# SCH_SCore-SR1_2024-12-18.net
KiCad netlist of a schematic drawn in EasyEDA
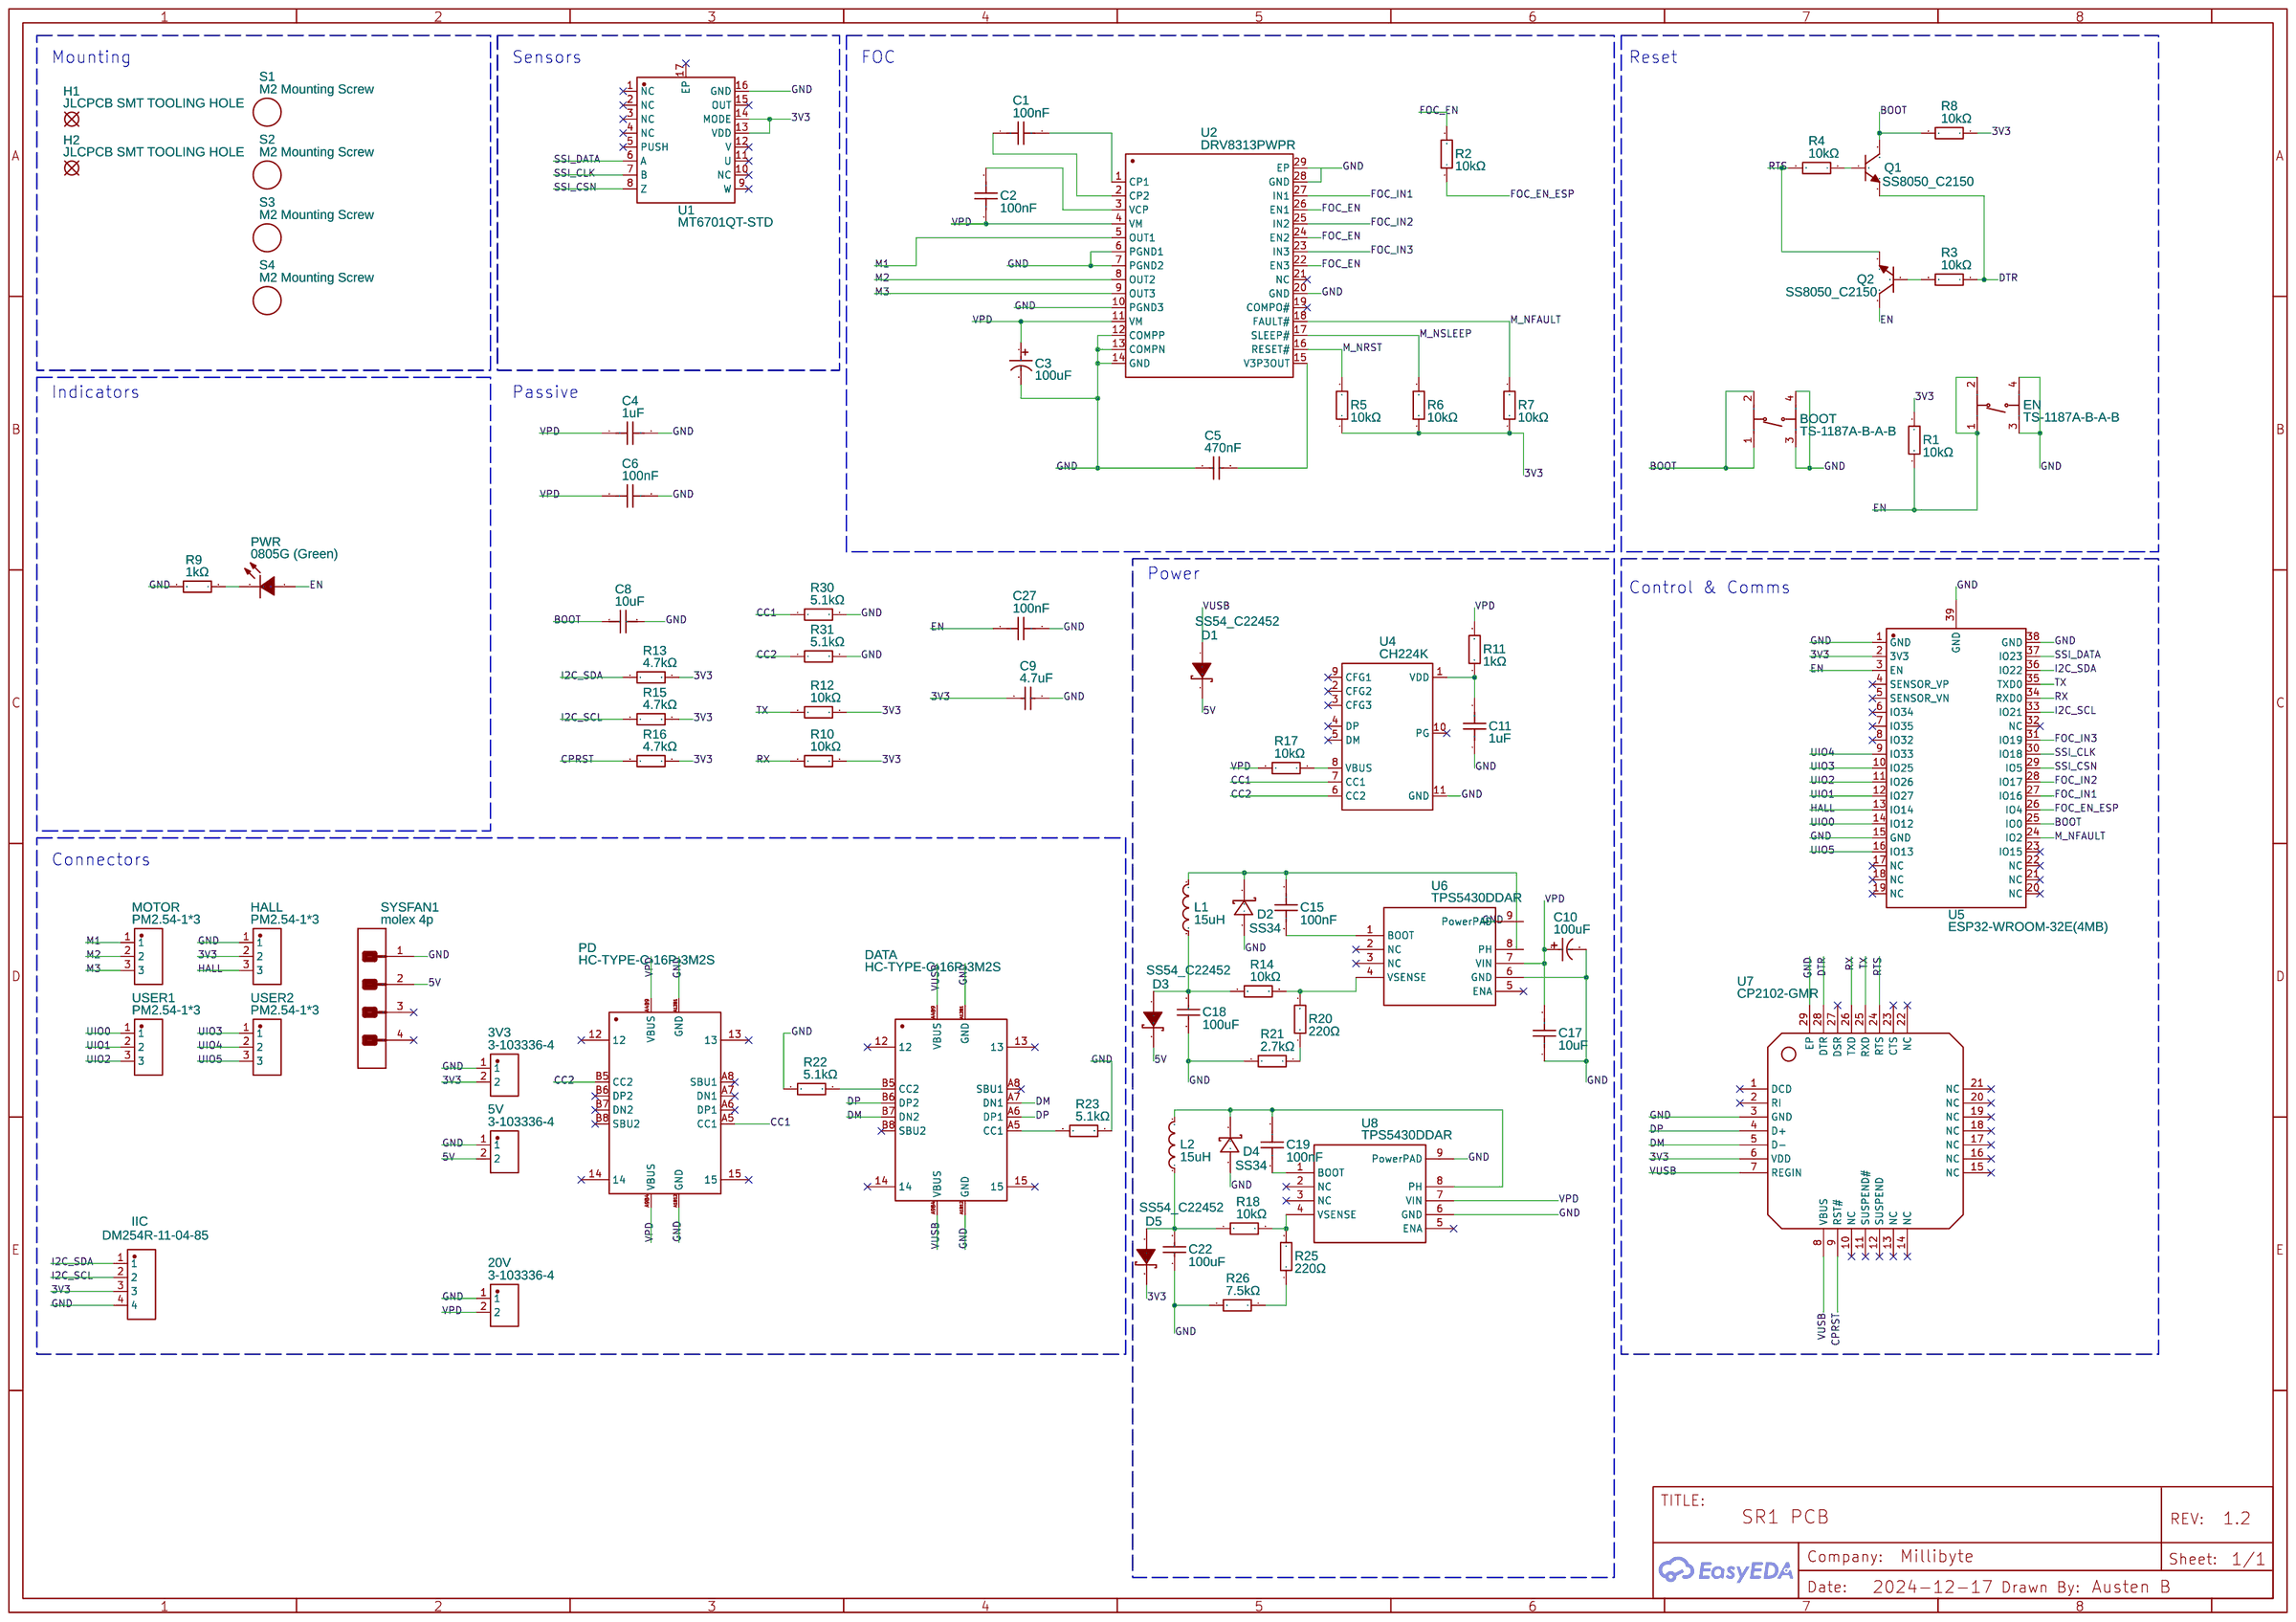
[diagram p0: schematic sheet]

(export (version "E")
  (design (tool "Eeschema 10.0.6"))
  (components
    (comp (ref "3V3")
      (value "3-103336-4")
      (fields (field (name "Manufacturer") "TE Connectivity(泰科电子)"))
      (libsource (lib "") (part "3-103336-4"))
    )
    (comp (ref "5V")
      (value "3-103336-4")
      (fields (field (name "Manufacturer") "TE Connectivity(泰科电子)"))
      (libsource (lib "") (part "3-103336-4_2"))
    )
    (comp (ref "20V")
      (value "3-103336-4")
      (fields (field (name "Manufacturer") "TE Connectivity(泰科电子)"))
      (libsource (lib "") (part "3-103336-4_1"))
    )
    (comp (ref "BOOT")
      (value "TS-1187A-B-A-B")
      (fields (field (name "Manufacturer") "XKB Connectivity(中国星坤)"))
      (libsource (lib "") (part "TS-1187A-B-A-B_1"))
    )
    (comp (ref "C1")
      (value "100nF")
      (fields
        (field (name "Manufacturer Part") "CC0603KRX7R9BB104")
        (field (name "Manufacturer") "YAGEO(国巨)")
      )
      (libsource (lib "") (part "CC0603KRX7R9BB104"))
    )
    (comp (ref "C2")
      (value "100nF")
      (fields
        (field (name "Manufacturer Part") "CC0603KRX7R9BB104")
        (field (name "Manufacturer") "YAGEO(国巨)")
      )
      (libsource (lib "") (part "CC0603KRX7R9BB104_2"))
    )
    (comp (ref "C3")
      (value "100uF")
      (fields (field (name "Manufacturer Part") "RT1V101M0607") (field (name "Manufacturer") "ROQANG(容强)"))
      (libsource (lib "") (part "RT1V101M0607"))
    )
    (comp (ref "C4")
      (value "1uF")
      (fields
        (field (name "Manufacturer Part") "CL10A105KB8NNNC")
        (field (name "Manufacturer") "SAMSUNG(三星)")
      )
      (libsource (lib "") (part "CL10A105KB8NNNC"))
    )
    (comp (ref "C5")
      (value "470nF")
      (fields
        (field (name "Manufacturer Part") "CL21B474KBFNNNE")
        (field (name "Manufacturer") "SAMSUNG(三星)")
      )
      (libsource (lib "") (part "CL21B474KBFNNNE"))
    )
    (comp (ref "C6")
      (value "100nF")
      (fields
        (field (name "Manufacturer Part") "CC0603KRX7R9BB104")
        (field (name "Manufacturer") "YAGEO(国巨)")
      )
      (libsource (lib "") (part "CC0603KRX7R9BB104"))
    )
    (comp (ref "C8")
      (value "10uF")
      (fields
        (field (name "Manufacturer Part") "CL10A106KP8NNNC")
        (field (name "Manufacturer") "SAMSUNG(三星)")
      )
      (libsource (lib "") (part "CL10A106KP8NNNC"))
    )
    (comp (ref "C9")
      (value "4.7uF")
      (fields
        (field (name "Manufacturer Part") "CL05A475MP5NRNC")
        (field (name "Manufacturer") "SAMSUNG(三星)")
      )
      (libsource (lib "") (part "CL05A475MP5NRNC"))
    )
    (comp (ref "C10")
      (value "100uF")
      (fields (field (name "Manufacturer Part") "RT1V101M0607") (field (name "Manufacturer") "ROQANG(容强)"))
      (libsource (lib "") (part "RT1V101M0607_1"))
    )
    (comp (ref "C11")
      (value "1uF")
      (fields
        (field (name "Manufacturer Part") "CL10A105KB8NNNC")
        (field (name "Manufacturer") "SAMSUNG(三星)")
      )
      (libsource (lib "") (part "CL10A105KB8NNNC_1"))
    )
    (comp (ref "C15")
      (value "100nF")
      (fields
        (field (name "Manufacturer Part") "CC0603KRX7R9BB104")
        (field (name "Manufacturer") "YAGEO(国巨)")
      )
      (libsource (lib "") (part "CC0603KRX7R9BB104_1"))
    )
    (comp (ref "C17")
      (value "10uF")
      (fields
        (field (name "Manufacturer Part") "CL21A106KAYNNNE")
        (field (name "Manufacturer") "SAMSUNG(三星)")
      )
      (libsource (lib "") (part "CL21A106KAYNNNE"))
    )
    (comp (ref "C18")
      (value "100uF")
      (fields
        (field (name "Manufacturer Part") "CL31A107MQHNNNE")
        (field (name "Manufacturer") "SAMSUNG(三星)")
      )
      (libsource (lib "") (part "CL31A107MQHNNNE"))
    )
    (comp (ref "C19")
      (value "100nF")
      (fields
        (field (name "Manufacturer Part") "CC0603KRX7R9BB104")
        (field (name "Manufacturer") "YAGEO(国巨)")
      )
      (libsource (lib "") (part "CC0603KRX7R9BB104_1"))
    )
    (comp (ref "C22")
      (value "100uF")
      (fields
        (field (name "Manufacturer Part") "CL31A107MQHNNNE")
        (field (name "Manufacturer") "SAMSUNG(三星)")
      )
      (libsource (lib "") (part "CL31A107MQHNNNE"))
    )
    (comp (ref "C27")
      (value "100nF")
      (fields
        (field (name "Manufacturer Part") "CC0603KRX7R9BB104")
        (field (name "Manufacturer") "YAGEO(国巨)")
      )
      (libsource (lib "") (part "CC0603KRX7R9BB104"))
    )
    (comp (ref "D1")
      (value "SS54_C22452")
      (fields (field (name "Manufacturer Part") "SS54") (field (name "Manufacturer") "MDD"))
      (libsource (lib "") (part "SS54_C22452"))
    )
    (comp (ref "D2")
      (value "SS34")
      (fields (field (name "Manufacturer") "MDD(辰达半导体)"))
      (libsource (lib "") (part "SS34_C8678"))
    )
    (comp (ref "D3")
      (value "SS54_C22452")
      (fields (field (name "Manufacturer Part") "SS54") (field (name "Manufacturer") "MDD"))
      (libsource (lib "") (part "SS54_C22452"))
    )
    (comp (ref "D4")
      (value "SS34")
      (fields (field (name "Manufacturer") "MDD(辰达半导体)"))
      (libsource (lib "") (part "SS34_C8678"))
    )
    (comp (ref "D5")
      (value "SS54_C22452")
      (fields (field (name "Manufacturer Part") "SS54") (field (name "Manufacturer") "MDD"))
      (libsource (lib "") (part "SS54_C22452"))
    )
    (comp (ref "DATA")
      (value "HC-TYPE-C-16P-3M2S")
      (fields (field (name "Manufacturer") "HC(虹成电子)"))
      (libsource (lib "") (part "HC-TYPE-C-16P-3M2S"))
    )
    (comp (ref "EN")
      (value "TS-1187A-B-A-B")
      (fields (field (name "Manufacturer") "XKB Connectivity(中国星坤)"))
      (libsource (lib "") (part "TS-1187A-B-A-B"))
    )
    (comp (ref "H1") (value "JLCPCB SMT TOOLING HOLE") (libsource (lib "") (part "JLCPCB SMT TOOLING HOLE")))
    (comp (ref "H2") (value "JLCPCB SMT TOOLING HOLE") (libsource (lib "") (part "JLCPCB SMT TOOLING HOLE")))
    (comp (ref "HALL")
      (value "PM2.54-1*3")
      (fields (field (name "Manufacturer") "ZHOURI(洲日)"))
      (libsource (lib "") (part "PM2.54-1*3"))
    )
    (comp (ref "IIC")
      (value "DM254R-11-04-85")
      (fields (field (name "Manufacturer") "DEALON(德艺隆)"))
      (libsource (lib "") (part "DM254R-11-04-85"))
    )
    (comp (ref "L1")
      (value "15uH")
      (fields
        (field (name "Manufacturer Part") "MWSA0603S-150MT")
        (field (name "Manufacturer") "Sunlord(顺络)")
      )
      (libsource (lib "") (part "MWSA0603S-150MT"))
    )
    (comp (ref "L2")
      (value "15uH")
      (fields
        (field (name "Manufacturer Part") "MWSA0603S-150MT")
        (field (name "Manufacturer") "Sunlord(顺络)")
      )
      (libsource (lib "") (part "MWSA0603S-150MT_1"))
    )
    (comp (ref "MOTOR")
      (value "PM2.54-1*3")
      (fields (field (name "Manufacturer") "ZHOURI(洲日)"))
      (libsource (lib "") (part "PM2.54-1*3_2"))
    )
    (comp (ref "PD")
      (value "HC-TYPE-C-16P-3M2S")
      (fields (field (name "Manufacturer") "HC(虹成电子)"))
      (libsource (lib "") (part "HC-TYPE-C-16P-3M2S_1"))
    )
    (comp (ref "PWR")
      (value "0805G (Green)")
      (fields (field (name "Manufacturer Part") "KT-0805G") (field (name "Manufacturer") "KENTO"))
      (libsource (lib "") (part "0805G (Green)"))
    )
    (comp (ref "Q1")
      (value "SS8050_C2150")
      (fields (field (name "Manufacturer Part") "SS8050") (field (name "Manufacturer") "CJ(江苏长电/长晶)"))
      (libsource (lib "") (part "SS8050_C2150"))
    )
    (comp (ref "Q2")
      (value "SS8050_C2150")
      (fields (field (name "Manufacturer Part") "SS8050") (field (name "Manufacturer") "CJ(江苏长电/长晶)"))
      (libsource (lib "") (part "SS8050_C2150_1"))
    )
    (comp (ref "R1")
      (value "10kΩ")
      (fields
        (field (name "Manufacturer Part") "0402WGF1002TCE")
        (field (name "Manufacturer") "UNI-ROYAL(厚声)")
      )
      (libsource (lib "") (part "0402WGF1002TCE_2"))
    )
    (comp (ref "R2")
      (value "10kΩ")
      (fields (field (name "Manufacturer Part") "0603WAF4701T5E") (field (name "Manufacturer") "UniOhm"))
      (libsource (lib "") (part "0603WAF4701T5E"))
    )
    (comp (ref "R3")
      (value "10kΩ")
      (fields
        (field (name "Manufacturer Part") "0402WGF1002TCE")
        (field (name "Manufacturer") "UNI-ROYAL(厚声)")
      )
      (libsource (lib "") (part "0402WGF1002TCE_1"))
    )
    (comp (ref "R4")
      (value "10kΩ")
      (fields
        (field (name "Manufacturer Part") "0402WGF1002TCE")
        (field (name "Manufacturer") "UNI-ROYAL(厚声)")
      )
      (libsource (lib "") (part "0402WGF1002TCE_1"))
    )
    (comp (ref "R5")
      (value "10kΩ")
      (fields
        (field (name "Manufacturer Part") "0402WGF1002TCE")
        (field (name "Manufacturer") "UNI-ROYAL(厚声)")
      )
      (libsource (lib "") (part "0402WGF1002TCE_2"))
    )
    (comp (ref "R6")
      (value "10kΩ")
      (fields
        (field (name "Manufacturer Part") "0402WGF1002TCE")
        (field (name "Manufacturer") "UNI-ROYAL(厚声)")
      )
      (libsource (lib "") (part "0402WGF1002TCE_2"))
    )
    (comp (ref "R7")
      (value "10kΩ")
      (fields
        (field (name "Manufacturer Part") "0402WGF1002TCE")
        (field (name "Manufacturer") "UNI-ROYAL(厚声)")
      )
      (libsource (lib "") (part "0402WGF1002TCE_2"))
    )
    (comp (ref "R8")
      (value "10kΩ")
      (fields
        (field (name "Manufacturer Part") "0402WGF1002TCE")
        (field (name "Manufacturer") "UNI-ROYAL(厚声)")
      )
      (libsource (lib "") (part "0402WGF1002TCE_1"))
    )
    (comp (ref "R9")
      (value "1kΩ")
      (fields
        (field (name "Manufacturer Part") "0402WGF1001TCE")
        (field (name "Manufacturer") "UNI-ROYAL(厚声)")
      )
      (libsource (lib "") (part "0402WGF1001TCE_1"))
    )
    (comp (ref "R10")
      (value "10kΩ")
      (fields
        (field (name "Manufacturer Part") "0402WGF1002TCE")
        (field (name "Manufacturer") "UNI-ROYAL(厚声)")
      )
      (libsource (lib "") (part "0402WGF1002TCE"))
    )
    (comp (ref "R11")
      (value "1kΩ")
      (fields
        (field (name "Manufacturer Part") "0402WGF1001TCE")
        (field (name "Manufacturer") "UNI-ROYAL(厚声)")
      )
      (libsource (lib "") (part "0402WGF1001TCE"))
    )
    (comp (ref "R12")
      (value "10kΩ")
      (fields
        (field (name "Manufacturer Part") "0402WGF1002TCE")
        (field (name "Manufacturer") "UNI-ROYAL(厚声)")
      )
      (libsource (lib "") (part "0402WGF1002TCE"))
    )
    (comp (ref "R13")
      (value "4.7kΩ")
      (fields
        (field (name "Manufacturer Part") "0402WGF4701TCE")
        (field (name "Manufacturer") "UNI-ROYAL(厚声)")
      )
      (libsource (lib "") (part "0402WGF4701TCE"))
    )
    (comp (ref "R14")
      (value "10kΩ")
      (fields
        (field (name "Manufacturer Part") "0402WGF1002TCE")
        (field (name "Manufacturer") "UNI-ROYAL(厚声)")
      )
      (libsource (lib "") (part "0402WGF1002TCE"))
    )
    (comp (ref "R15")
      (value "4.7kΩ")
      (fields
        (field (name "Manufacturer Part") "0402WGF4701TCE")
        (field (name "Manufacturer") "UNI-ROYAL(厚声)")
      )
      (libsource (lib "") (part "0402WGF4701TCE"))
    )
    (comp (ref "R16")
      (value "4.7kΩ")
      (fields
        (field (name "Manufacturer Part") "0402WGF4701TCE")
        (field (name "Manufacturer") "UNI-ROYAL(厚声)")
      )
      (libsource (lib "") (part "0402WGF4701TCE"))
    )
    (comp (ref "R17")
      (value "10kΩ")
      (fields
        (field (name "Manufacturer Part") "0402WGF1002TCE")
        (field (name "Manufacturer") "UNI-ROYAL(厚声)")
      )
      (libsource (lib "") (part "0402WGF1002TCE_1"))
    )
    (comp (ref "R18")
      (value "10kΩ")
      (fields
        (field (name "Manufacturer Part") "0402WGF1002TCE")
        (field (name "Manufacturer") "UNI-ROYAL(厚声)")
      )
      (libsource (lib "") (part "0402WGF1002TCE"))
    )
    (comp (ref "R20")
      (value "220Ω")
      (fields
        (field (name "Manufacturer Part") "0603WAF2200T5E")
        (field (name "Manufacturer") "UNI-ROYAL(厚声)")
      )
      (libsource (lib "") (part "0603WAF2200T5E"))
    )
    (comp (ref "R21")
      (value "2.7kΩ")
      (fields (field (name "Manufacturer Part") "0603WAF2701T5E") (field (name "Manufacturer") "UniOhm"))
      (libsource (lib "") (part "0603WAF2701T5E"))
    )
    (comp (ref "R22")
      (value "5.1kΩ")
      (fields
        (field (name "Manufacturer Part") "0402WGF5101TCE")
        (field (name "Manufacturer") "UNI-ROYAL(厚声)")
      )
      (libsource (lib "") (part "0402WGF5101TCE"))
    )
    (comp (ref "R23")
      (value "5.1kΩ")
      (fields
        (field (name "Manufacturer Part") "0402WGF5101TCE")
        (field (name "Manufacturer") "UNI-ROYAL(厚声)")
      )
      (libsource (lib "") (part "0402WGF5101TCE"))
    )
    (comp (ref "R25")
      (value "220Ω")
      (fields
        (field (name "Manufacturer Part") "0603WAF2200T5E")
        (field (name "Manufacturer") "UNI-ROYAL(厚声)")
      )
      (libsource (lib "") (part "0603WAF2200T5E"))
    )
    (comp (ref "R26")
      (value "7.5kΩ")
      (fields (field (name "Manufacturer Part") "0603WAF7501T5E") (field (name "Manufacturer") "UniOhm"))
      (libsource (lib "") (part "0603WAF7501T5E"))
    )
    (comp (ref "R30")
      (value "5.1kΩ")
      (fields
        (field (name "Manufacturer Part") "0402WGF5101TCE")
        (field (name "Manufacturer") "UNI-ROYAL(厚声)")
      )
      (libsource (lib "") (part "0402WGF5101TCE"))
    )
    (comp (ref "R31")
      (value "5.1kΩ")
      (fields
        (field (name "Manufacturer Part") "0402WGF5101TCE")
        (field (name "Manufacturer") "UNI-ROYAL(厚声)")
      )
      (libsource (lib "") (part "0402WGF5101TCE"))
    )
    (comp (ref "S1") (value "M2 Mounting Screw") (libsource (lib "") (part "M2 Mounting Screw")))
    (comp (ref "S2") (value "M2 Mounting Screw") (libsource (lib "") (part "M2 Mounting Screw")))
    (comp (ref "S3") (value "M2 Mounting Screw") (libsource (lib "") (part "M2 Mounting Screw")))
    (comp (ref "S4") (value "M2 Mounting Screw") (libsource (lib "") (part "M2 Mounting Screw")))
    (comp (ref "SYSFAN1") (value "molex 4p") (libsource (lib "") (part "molex 4p")))
    (comp (ref "U1")
      (value "MT6701QT-STD")
      (fields (field (name "Manufacturer") "MagnTek(麦歌恩)"))
      (libsource (lib "") (part "MT6701QT-STD"))
    )
    (comp (ref "U2")
      (value "DRV8313PWPR")
      (fields (field (name "Manufacturer") "Texas Instruments"))
      (libsource (lib "") (part "DRV8313PWPR"))
    )
    (comp (ref "U4")
      (value "CH224K")
      (fields (field (name "Manufacturer") "WCH(南京沁恒)"))
      (libsource (lib "") (part "CH224K"))
    )
    (comp (ref "U5")
      (value "ESP32-WROOM-32E(4MB)")
      (fields
        (field (name "Manufacturer Part") "ESP32-WROOM-32E-N4")
        (field (name "Manufacturer") "ESPRESSIF(乐鑫)")
      )
      (libsource (lib "") (part "ESP32-WROOM-32E(4MB)"))
    )
    (comp (ref "U6")
      (value "TPS5430DDAR")
      (fields (field (name "Manufacturer") "TI(德州仪器)"))
      (libsource (lib "") (part "TPS5430DDAR"))
    )
    (comp (ref "U7")
      (value "CP2102-GMR")
      (fields (field (name "Manufacturer") "SKYWORKS/SILICON LABS(芯科)"))
      (libsource (lib "") (part "CP2102-GMR"))
    )
    (comp (ref "U8")
      (value "TPS5430DDAR")
      (fields (field (name "Manufacturer") "TI(德州仪器)"))
      (libsource (lib "") (part "TPS5430DDAR"))
    )
    (comp (ref "USER1")
      (value "PM2.54-1*3")
      (fields (field (name "Manufacturer") "ZHOURI(洲日)"))
      (libsource (lib "") (part "PM2.54-1*3_1"))
    )
    (comp (ref "USER2")
      (value "PM2.54-1*3")
      (fields (field (name "Manufacturer") "ZHOURI(洲日)"))
      (libsource (lib "") (part "PM2.54-1*3_1"))
    )
  )
  (nets
    (net (code "1") (name "/3V3") (class "Default")
      (node (ref "3V3") (pin "2") (pinfunction "2_2") (pintype "unspecified"))
      (node (ref "C9") (pin "1") (pinfunction "1_1") (pintype "input"))
      (node (ref "D5") (pin "2") (pinfunction "K_2") (pintype "unspecified"))
      (node (ref "HALL") (pin "2") (pinfunction "2_2") (pintype "unspecified"))
      (node (ref "IIC") (pin "3") (pinfunction "3_3") (pintype "unspecified"))
      (node (ref "R1") (pin "2") (pinfunction "2_2") (pintype "input"))
      (node (ref "R10") (pin "2") (pinfunction "2_2") (pintype "input"))
      (node (ref "R12") (pin "2") (pinfunction "2_2") (pintype "input"))
      (node (ref "R13") (pin "2") (pinfunction "2_2") (pintype "input"))
      (node (ref "R15") (pin "2") (pinfunction "2_2") (pintype "input"))
      (node (ref "R16") (pin "2") (pinfunction "2_2") (pintype "input"))
      (node (ref "R5") (pin "1") (pinfunction "1_1") (pintype "input"))
      (node (ref "R6") (pin "1") (pinfunction "1_1") (pintype "input"))
      (node (ref "R7") (pin "1") (pinfunction "1_1") (pintype "input"))
      (node (ref "R8") (pin "1") (pinfunction "1_1") (pintype "input"))
      (node (ref "U1") (pin "13") (pinfunction "VDD_13") (pintype "unspecified"))
      (node (ref "U1") (pin "14") (pinfunction "MODE_14") (pintype "unspecified"))
      (node (ref "U5") (pin "2") (pinfunction "3V3_2") (pintype "unspecified"))
      (node (ref "U7") (pin "6") (pinfunction "VDD_6") (pintype "unspecified"))
    )
    (net (code "2") (name "/5V") (class "Default")
      (node (ref "5V") (pin "2") (pinfunction "2_2") (pintype "unspecified"))
      (node (ref "D1") (pin "2") (pinfunction "K_2") (pintype "unspecified"))
      (node (ref "D3") (pin "2") (pinfunction "K_2") (pintype "unspecified"))
      (node (ref "SYSFAN1") (pin "2") (pinfunction "2_2") (pintype "bidirectional"))
    )
    (net (code "3") (name "/BOOT") (class "Default")
      (node (ref "BOOT") (pin "1") (pinfunction "A_1") (pintype "unspecified"))
      (node (ref "BOOT") (pin "2") (pinfunction "B_2") (pintype "unspecified"))
      (node (ref "C8") (pin "1") (pinfunction "1_1") (pintype "unspecified"))
      (node (ref "Q1") (pin "3") (pinfunction "C_3") (pintype "unspecified"))
      (node (ref "R8") (pin "2") (pinfunction "2_2") (pintype "input"))
      (node (ref "U5") (pin "25") (pinfunction "IO0_25") (pintype "unspecified"))
    )
    (net (code "4") (name "/CC1") (class "Default")
      (node (ref "PD") (pin "A5") (pinfunction "CC1_A5") (pintype "unspecified"))
      (node (ref "R30") (pin "1") (pinfunction "1_1") (pintype "input"))
      (node (ref "U4") (pin "7") (pinfunction "CC1_7") (pintype "unspecified"))
    )
    (net (code "5") (name "/CC2") (class "Default")
      (node (ref "PD") (pin "B5") (pinfunction "CC2_B5") (pintype "unspecified"))
      (node (ref "R31") (pin "1") (pinfunction "1_1") (pintype "input"))
      (node (ref "U4") (pin "6") (pinfunction "CC2_6") (pintype "unspecified"))
    )
    (net (code "6") (name "/CPRST") (class "Default")
      (node (ref "R16") (pin "1") (pinfunction "1_1") (pintype "input"))
      (node (ref "U7") (pin "9") (pinfunction "RST#_9") (pintype "unspecified"))
    )
    (net (code "7") (name "/DM") (class "Default")
      (node (ref "DATA") (pin "A7") (pinfunction "DN1_A7") (pintype "unspecified"))
      (node (ref "DATA") (pin "B7") (pinfunction "DN2_B7") (pintype "unspecified"))
      (node (ref "U7") (pin "5") (pinfunction "D-_5") (pintype "unspecified"))
    )
    (net (code "8") (name "/DP") (class "Default")
      (node (ref "DATA") (pin "A6") (pinfunction "DP1_A6") (pintype "unspecified"))
      (node (ref "DATA") (pin "B6") (pinfunction "DP2_B6") (pintype "unspecified"))
      (node (ref "U7") (pin "4") (pinfunction "D+_4") (pintype "unspecified"))
    )
    (net (code "9") (name "/DTR") (class "Default")
      (node (ref "Q1") (pin "2") (pinfunction "E_2") (pintype "unspecified"))
      (node (ref "R3") (pin "1") (pinfunction "1_1") (pintype "input"))
      (node (ref "U7") (pin "28") (pinfunction "DTR_28") (pintype "unspecified"))
    )
    (net (code "10") (name "/EN") (class "Default")
      (node (ref "C27") (pin "1") (pinfunction "1_1") (pintype "unspecified"))
      (node (ref "EN") (pin "1") (pinfunction "A_1") (pintype "unspecified"))
      (node (ref "EN") (pin "2") (pinfunction "B_2") (pintype "unspecified"))
      (node (ref "PWR") (pin "1") (pinfunction "A_1") (pintype "unspecified"))
      (node (ref "Q2") (pin "3") (pinfunction "C_3") (pintype "unspecified"))
      (node (ref "R1") (pin "1") (pinfunction "1_1") (pintype "input"))
      (node (ref "U5") (pin "3") (pinfunction "EN_3") (pintype "unspecified"))
    )
    (net (code "11") (name "/FOC_EN") (class "Default")
      (node (ref "R2") (pin "2") (pinfunction "2_2") (pintype "input"))
      (node (ref "U2") (pin "22") (pinfunction "EN3_22") (pintype "unspecified"))
      (node (ref "U2") (pin "24") (pinfunction "EN2_24") (pintype "unspecified"))
      (node (ref "U2") (pin "26") (pinfunction "EN1_26") (pintype "unspecified"))
    )
    (net (code "12") (name "/FOC_EN_ESP") (class "Default")
      (node (ref "R2") (pin "1") (pinfunction "1_1") (pintype "input"))
      (node (ref "U5") (pin "26") (pinfunction "IO4_26") (pintype "unspecified"))
    )
    (net (code "13") (name "/FOC_IN1") (class "Default")
      (node (ref "U2") (pin "27") (pinfunction "IN1_27") (pintype "unspecified"))
      (node (ref "U5") (pin "27") (pinfunction "IO16_27") (pintype "unspecified"))
    )
    (net (code "14") (name "/FOC_IN2") (class "Default")
      (node (ref "U2") (pin "25") (pinfunction "IN2_25") (pintype "unspecified"))
      (node (ref "U5") (pin "28") (pinfunction "IO17_28") (pintype "unspecified"))
    )
    (net (code "15") (name "/FOC_IN3") (class "Default")
      (node (ref "U2") (pin "23") (pinfunction "IN3_23") (pintype "unspecified"))
      (node (ref "U5") (pin "31") (pinfunction "IO19_31") (pintype "unspecified"))
    )
    (net (code "16") (name "/GND") (class "Default")
      (node (ref "20V") (pin "1") (pinfunction "1_1") (pintype "unspecified"))
      (node (ref "3V3") (pin "1") (pinfunction "1_1") (pintype "unspecified"))
      (node (ref "5V") (pin "1") (pinfunction "1_1") (pintype "unspecified"))
      (node (ref "BOOT") (pin "3") (pinfunction "C_3") (pintype "unspecified"))
      (node (ref "BOOT") (pin "4") (pinfunction "D_4") (pintype "unspecified"))
      (node (ref "C10") (pin "2") (pinfunction "2_2") (pintype "input"))
      (node (ref "C11") (pin "1") (pinfunction "1_1") (pintype "unspecified"))
      (node (ref "C17") (pin "1") (pinfunction "1_1") (pintype "unspecified"))
      (node (ref "C18") (pin "1") (pinfunction "1_1") (pintype "input"))
      (node (ref "C22") (pin "1") (pinfunction "1_1") (pintype "input"))
      (node (ref "C27") (pin "2") (pinfunction "2_2") (pintype "unspecified"))
      (node (ref "C3") (pin "2") (pinfunction "2_2") (pintype "input"))
      (node (ref "C4") (pin "2") (pinfunction "2_2") (pintype "unspecified"))
      (node (ref "C5") (pin "1") (pinfunction "1_1") (pintype "unspecified"))
      (node (ref "C6") (pin "2") (pinfunction "2_2") (pintype "unspecified"))
      (node (ref "C8") (pin "2") (pinfunction "2_2") (pintype "unspecified"))
      (node (ref "C9") (pin "2") (pinfunction "2_2") (pintype "input"))
      (node (ref "D2") (pin "2") (pinfunction "A_2") (pintype "unspecified"))
      (node (ref "D4") (pin "2") (pinfunction "A_2") (pintype "unspecified"))
      (node (ref "DATA") (pin "A12B1") (pinfunction "GND_A12B1") (pintype "unspecified"))
      (node (ref "DATA") (pin "A1B12") (pinfunction "GND_A1B12") (pintype "unspecified"))
      (node (ref "EN") (pin "3") (pinfunction "C_3") (pintype "unspecified"))
      (node (ref "EN") (pin "4") (pinfunction "D_4") (pintype "unspecified"))
      (node (ref "HALL") (pin "1") (pinfunction "1_1") (pintype "unspecified"))
      (node (ref "IIC") (pin "4") (pinfunction "4_4") (pintype "unspecified"))
      (node (ref "PD") (pin "A12B1") (pinfunction "GND_A12B1") (pintype "unspecified"))
      (node (ref "PD") (pin "A1B12") (pinfunction "GND_A1B12") (pintype "unspecified"))
      (node (ref "R21") (pin "2") (pinfunction "2_2") (pintype "unspecified"))
      (node (ref "R22") (pin "1") (pinfunction "1_1") (pintype "input"))
      (node (ref "R23") (pin "2") (pinfunction "2_2") (pintype "input"))
      (node (ref "R26") (pin "2") (pinfunction "2_2") (pintype "unspecified"))
      (node (ref "R30") (pin "2") (pinfunction "2_2") (pintype "input"))
      (node (ref "R31") (pin "2") (pinfunction "2_2") (pintype "input"))
      (node (ref "R9") (pin "2") (pinfunction "2_2") (pintype "input"))
      (node (ref "SYSFAN1") (pin "1") (pinfunction "1_1") (pintype "bidirectional"))
      (node (ref "U1") (pin "16") (pinfunction "GND_16") (pintype "unspecified"))
      (node (ref "U2") (pin "10") (pinfunction "PGND3_10") (pintype "unspecified"))
      (node (ref "U2") (pin "12") (pinfunction "COMPP_12") (pintype "unspecified"))
      (node (ref "U2") (pin "13") (pinfunction "COMPN_13") (pintype "unspecified"))
      (node (ref "U2") (pin "14") (pinfunction "GND_14") (pintype "unspecified"))
      (node (ref "U2") (pin "20") (pinfunction "GND_20") (pintype "unspecified"))
      (node (ref "U2") (pin "28") (pinfunction "GND_28") (pintype "unspecified"))
      (node (ref "U2") (pin "29") (pinfunction "EP_29") (pintype "unspecified"))
      (node (ref "U2") (pin "6") (pinfunction "PGND1_6") (pintype "unspecified"))
      (node (ref "U2") (pin "7") (pinfunction "PGND2_7") (pintype "unspecified"))
      (node (ref "U4") (pin "11") (pinfunction "GND_11") (pintype "unspecified"))
      (node (ref "U5") (pin "1") (pinfunction "GND_1") (pintype "unspecified"))
      (node (ref "U5") (pin "15") (pinfunction "GND_15") (pintype "unspecified"))
      (node (ref "U5") (pin "38") (pinfunction "GND_38") (pintype "unspecified"))
      (node (ref "U5") (pin "39") (pinfunction "GND_39") (pintype "unspecified"))
      (node (ref "U6") (pin "6") (pinfunction "GND_6") (pintype "unspecified"))
      (node (ref "U6") (pin "9") (pinfunction "PowerPAD_9") (pintype "unspecified"))
      (node (ref "U7") (pin "29") (pinfunction "EP_29") (pintype "unspecified"))
      (node (ref "U7") (pin "3") (pinfunction "GND_3") (pintype "unspecified"))
      (node (ref "U8") (pin "6") (pinfunction "GND_6") (pintype "unspecified"))
      (node (ref "U8") (pin "9") (pinfunction "PowerPAD_9") (pintype "unspecified"))
    )
    (net (code "17") (name "/HALL") (class "Default")
      (node (ref "HALL") (pin "3") (pinfunction "3_3") (pintype "unspecified"))
      (node (ref "U5") (pin "13") (pinfunction "IO14_13") (pintype "unspecified"))
    )
    (net (code "18") (name "/I2C_SCL") (class "Default")
      (node (ref "IIC") (pin "2") (pinfunction "2_2") (pintype "unspecified"))
      (node (ref "R15") (pin "1") (pinfunction "1_1") (pintype "input"))
      (node (ref "U5") (pin "33") (pinfunction "IO21_33") (pintype "unspecified"))
    )
    (net (code "19") (name "/I2C_SDA") (class "Default")
      (node (ref "IIC") (pin "1") (pinfunction "1_1") (pintype "unspecified"))
      (node (ref "R13") (pin "1") (pinfunction "1_1") (pintype "input"))
      (node (ref "U5") (pin "36") (pinfunction "IO22_36") (pintype "unspecified"))
    )
    (net (code "20") (name "/M1") (class "Default")
      (node (ref "MOTOR") (pin "1") (pinfunction "1_1") (pintype "unspecified"))
      (node (ref "U2") (pin "5") (pinfunction "OUT1_5") (pintype "unspecified"))
    )
    (net (code "21") (name "/M2") (class "Default")
      (node (ref "MOTOR") (pin "2") (pinfunction "2_2") (pintype "unspecified"))
      (node (ref "U2") (pin "8") (pinfunction "OUT2_8") (pintype "unspecified"))
    )
    (net (code "22") (name "/M3") (class "Default")
      (node (ref "MOTOR") (pin "3") (pinfunction "3_3") (pintype "unspecified"))
      (node (ref "U2") (pin "9") (pinfunction "OUT3_9") (pintype "unspecified"))
    )
    (net (code "23") (name "/M_NFAULT") (class "Default")
      (node (ref "R7") (pin "2") (pinfunction "2_2") (pintype "input"))
      (node (ref "U2") (pin "18") (pinfunction "FAULT#_18") (pintype "unspecified"))
      (node (ref "U5") (pin "24") (pinfunction "IO2_24") (pintype "unspecified"))
    )
    (net (code "24") (name "/M_NRST") (class "Default")
      (node (ref "R5") (pin "2") (pinfunction "2_2") (pintype "input"))
      (node (ref "U2") (pin "16") (pinfunction "RESET#_16") (pintype "unspecified"))
    )
    (net (code "25") (name "/M_NSLEEP") (class "Default")
      (node (ref "R6") (pin "2") (pinfunction "2_2") (pintype "input"))
      (node (ref "U2") (pin "17") (pinfunction "SLEEP#_17") (pintype "unspecified"))
    )
    (net (code "26") (name "/RTS") (class "Default")
      (node (ref "Q2") (pin "2") (pinfunction "E_2") (pintype "unspecified"))
      (node (ref "R4") (pin "2") (pinfunction "2_2") (pintype "input"))
      (node (ref "U7") (pin "24") (pinfunction "RTS_24") (pintype "unspecified"))
    )
    (net (code "27") (name "/RX") (class "Default")
      (node (ref "R10") (pin "1") (pinfunction "1_1") (pintype "input"))
      (node (ref "U5") (pin "34") (pinfunction "RXD0_34") (pintype "unspecified"))
      (node (ref "U7") (pin "26") (pinfunction "TXD_26") (pintype "unspecified"))
    )
    (net (code "28") (name "/SSI_CLK") (class "Default")
      (node (ref "U1") (pin "7") (pinfunction "B_7") (pintype "unspecified"))
      (node (ref "U5") (pin "30") (pinfunction "IO18_30") (pintype "unspecified"))
    )
    (net (code "29") (name "/SSI_CSN") (class "Default")
      (node (ref "U1") (pin "8") (pinfunction "Z_8") (pintype "unspecified"))
      (node (ref "U5") (pin "29") (pinfunction "IO5_29") (pintype "unspecified"))
    )
    (net (code "30") (name "/SSI_DATA") (class "Default")
      (node (ref "U1") (pin "6") (pinfunction "A_6") (pintype "unspecified"))
      (node (ref "U5") (pin "37") (pinfunction "IO23_37") (pintype "unspecified"))
    )
    (net (code "31") (name "/TX") (class "Default")
      (node (ref "R12") (pin "1") (pinfunction "1_1") (pintype "input"))
      (node (ref "U5") (pin "35") (pinfunction "TXD0_35") (pintype "unspecified"))
      (node (ref "U7") (pin "25") (pinfunction "RXD_25") (pintype "unspecified"))
    )
    (net (code "32") (name "/UIO0") (class "Default")
      (node (ref "U5") (pin "14") (pinfunction "IO12_14") (pintype "unspecified"))
      (node (ref "USER1") (pin "1") (pinfunction "1_1") (pintype "unspecified"))
    )
    (net (code "33") (name "/UIO1") (class "Default")
      (node (ref "U5") (pin "12") (pinfunction "IO27_12") (pintype "unspecified"))
      (node (ref "USER1") (pin "2") (pinfunction "2_2") (pintype "unspecified"))
    )
    (net (code "34") (name "/UIO2") (class "Default")
      (node (ref "U5") (pin "11") (pinfunction "IO26_11") (pintype "unspecified"))
      (node (ref "USER1") (pin "3") (pinfunction "3_3") (pintype "unspecified"))
    )
    (net (code "35") (name "/UIO3") (class "Default")
      (node (ref "U5") (pin "10") (pinfunction "IO25_10") (pintype "unspecified"))
      (node (ref "USER2") (pin "1") (pinfunction "1_1") (pintype "unspecified"))
    )
    (net (code "36") (name "/UIO4") (class "Default")
      (node (ref "U5") (pin "9") (pinfunction "IO33_9") (pintype "unspecified"))
      (node (ref "USER2") (pin "2") (pinfunction "2_2") (pintype "unspecified"))
    )
    (net (code "37") (name "/UIO5") (class "Default")
      (node (ref "U5") (pin "16") (pinfunction "IO13_16") (pintype "unspecified"))
      (node (ref "USER2") (pin "3") (pinfunction "3_3") (pintype "unspecified"))
    )
    (net (code "38") (name "/VPD") (class "Default")
      (node (ref "20V") (pin "2") (pinfunction "2_2") (pintype "unspecified"))
      (node (ref "C10") (pin "1") (pinfunction "1_1") (pintype "input"))
      (node (ref "C17") (pin "2") (pinfunction "2_2") (pintype "unspecified"))
      (node (ref "C2") (pin "1") (pinfunction "1_1") (pintype "unspecified"))
      (node (ref "C3") (pin "1") (pinfunction "1_1") (pintype "input"))
      (node (ref "C4") (pin "1") (pinfunction "1_1") (pintype "unspecified"))
      (node (ref "C6") (pin "1") (pinfunction "1_1") (pintype "unspecified"))
      (node (ref "PD") (pin "A4B9") (pinfunction "VBUS_A4B9") (pintype "unspecified"))
      (node (ref "PD") (pin "A9B4") (pinfunction "VBUS_A9B4") (pintype "unspecified"))
      (node (ref "R11") (pin "2") (pinfunction "2_2") (pintype "input"))
      (node (ref "R17") (pin "2") (pinfunction "2_2") (pintype "input"))
      (node (ref "U2") (pin "11") (pinfunction "VM_11") (pintype "unspecified"))
      (node (ref "U2") (pin "4") (pinfunction "VM_4") (pintype "unspecified"))
      (node (ref "U6") (pin "7") (pinfunction "VIN_7") (pintype "unspecified"))
      (node (ref "U8") (pin "7") (pinfunction "VIN_7") (pintype "unspecified"))
    )
    (net (code "39") (name "/VUSB") (class "Default")
      (node (ref "D1") (pin "1") (pinfunction "A_1") (pintype "unspecified"))
      (node (ref "DATA") (pin "A4B9") (pinfunction "VBUS_A4B9") (pintype "unspecified"))
      (node (ref "DATA") (pin "A9B4") (pinfunction "VBUS_A9B4") (pintype "unspecified"))
      (node (ref "U7") (pin "7") (pinfunction "REGIN_7") (pintype "unspecified"))
      (node (ref "U7") (pin "8") (pinfunction "VBUS_8") (pintype "unspecified"))
    )
    (net (code "40") (name "Net-(D2-K)") (class "Default")
      (node (ref "C15") (pin "1") (pinfunction "1_1") (pintype "unspecified"))
      (node (ref "D2") (pin "1") (pinfunction "K_1") (pintype "unspecified"))
      (node (ref "L1") (pin "2") (pinfunction "2_2") (pintype "unspecified"))
      (node (ref "U6") (pin "8") (pinfunction "PH_8") (pintype "unspecified"))
    )
    (net (code "41") (name "Net-(D3-A)") (class "Default")
      (node (ref "C18") (pin "2") (pinfunction "2_2") (pintype "input"))
      (node (ref "D3") (pin "1") (pinfunction "A_1") (pintype "unspecified"))
      (node (ref "L1") (pin "1") (pinfunction "1_1") (pintype "unspecified"))
      (node (ref "R14") (pin "1") (pinfunction "1_1") (pintype "input"))
    )
    (net (code "42") (name "Net-(D4-K)") (class "Default")
      (node (ref "C19") (pin "1") (pinfunction "1_1") (pintype "unspecified"))
      (node (ref "D4") (pin "1") (pinfunction "K_1") (pintype "unspecified"))
      (node (ref "L2") (pin "2") (pinfunction "2_2") (pintype "unspecified"))
      (node (ref "U8") (pin "8") (pinfunction "PH_8") (pintype "unspecified"))
    )
    (net (code "43") (name "Net-(D5-A)") (class "Default")
      (node (ref "C22") (pin "2") (pinfunction "2_2") (pintype "input"))
      (node (ref "D5") (pin "1") (pinfunction "A_1") (pintype "unspecified"))
      (node (ref "L2") (pin "1") (pinfunction "1_1") (pintype "unspecified"))
      (node (ref "R18") (pin "1") (pinfunction "1_1") (pintype "input"))
    )
    (net (code "44") (name "Net-(DATA-CC1)") (class "Default")
      (node (ref "DATA") (pin "A5") (pinfunction "CC1_A5") (pintype "unspecified"))
      (node (ref "R23") (pin "1") (pinfunction "1_1") (pintype "input"))
    )
    (net (code "45") (name "Net-(DATA-CC2)") (class "Default")
      (node (ref "DATA") (pin "B5") (pinfunction "CC2_B5") (pintype "unspecified"))
      (node (ref "R22") (pin "2") (pinfunction "2_2") (pintype "input"))
    )
    (net (code "46") (name "Net-(PWR-K)") (class "Default")
      (node (ref "PWR") (pin "2") (pinfunction "K_2") (pintype "unspecified"))
      (node (ref "R9") (pin "1") (pinfunction "1_1") (pintype "input"))
    )
    (net (code "47") (name "Net-(Q1-B)") (class "Default")
      (node (ref "Q1") (pin "1") (pinfunction "B_1") (pintype "unspecified"))
      (node (ref "R4") (pin "1") (pinfunction "1_1") (pintype "input"))
    )
    (net (code "48") (name "Net-(Q2-B)") (class "Default")
      (node (ref "Q2") (pin "1") (pinfunction "B_1") (pintype "unspecified"))
      (node (ref "R3") (pin "2") (pinfunction "2_2") (pintype "input"))
    )
    (net (code "49") (name "Net-(R20-Pad1)") (class "Default")
      (node (ref "R20") (pin "1") (pinfunction "1_1") (pintype "input"))
      (node (ref "R21") (pin "1") (pinfunction "1_1") (pintype "unspecified"))
    )
    (net (code "50") (name "Net-(R25-Pad1)") (class "Default")
      (node (ref "R25") (pin "1") (pinfunction "1_1") (pintype "input"))
      (node (ref "R26") (pin "1") (pinfunction "1_1") (pintype "unspecified"))
    )
    (net (code "51") (name "Net-(U2-CP1)") (class "Default")
      (node (ref "C1") (pin "2") (pinfunction "2_2") (pintype "unspecified"))
      (node (ref "U2") (pin "1") (pinfunction "CP1_1") (pintype "unspecified"))
    )
    (net (code "52") (name "Net-(U2-CP2)") (class "Default")
      (node (ref "C1") (pin "1") (pinfunction "1_1") (pintype "unspecified"))
      (node (ref "U2") (pin "2") (pinfunction "CP2_2") (pintype "unspecified"))
    )
    (net (code "53") (name "Net-(U2-V3P3OUT)") (class "Default")
      (node (ref "C5") (pin "2") (pinfunction "2_2") (pintype "unspecified"))
      (node (ref "U2") (pin "15") (pinfunction "V3P3OUT_15") (pintype "unspecified"))
    )
    (net (code "54") (name "Net-(U2-VCP)") (class "Default")
      (node (ref "C2") (pin "2") (pinfunction "2_2") (pintype "unspecified"))
      (node (ref "U2") (pin "3") (pinfunction "VCP_3") (pintype "unspecified"))
    )
    (net (code "55") (name "Net-(U4-VBUS)") (class "Default")
      (node (ref "R17") (pin "1") (pinfunction "1_1") (pintype "input"))
      (node (ref "U4") (pin "8") (pinfunction "VBUS_8") (pintype "unspecified"))
    )
    (net (code "56") (name "Net-(U4-VDD)") (class "Default")
      (node (ref "C11") (pin "2") (pinfunction "2_2") (pintype "unspecified"))
      (node (ref "R11") (pin "1") (pinfunction "1_1") (pintype "input"))
      (node (ref "U4") (pin "1") (pinfunction "VDD_1") (pintype "unspecified"))
    )
    (net (code "57") (name "Net-(U6-BOOT)") (class "Default")
      (node (ref "C15") (pin "2") (pinfunction "2_2") (pintype "unspecified"))
      (node (ref "U6") (pin "1") (pinfunction "BOOT_1") (pintype "unspecified"))
    )
    (net (code "58") (name "Net-(U6-VSENSE)") (class "Default")
      (node (ref "R14") (pin "2") (pinfunction "2_2") (pintype "input"))
      (node (ref "R20") (pin "2") (pinfunction "2_2") (pintype "input"))
      (node (ref "U6") (pin "4") (pinfunction "VSENSE_4") (pintype "unspecified"))
    )
    (net (code "59") (name "Net-(U8-BOOT)") (class "Default")
      (node (ref "C19") (pin "2") (pinfunction "2_2") (pintype "unspecified"))
      (node (ref "U8") (pin "1") (pinfunction "BOOT_1") (pintype "unspecified"))
    )
    (net (code "60") (name "Net-(U8-VSENSE)") (class "Default")
      (node (ref "R18") (pin "2") (pinfunction "2_2") (pintype "input"))
      (node (ref "R25") (pin "2") (pinfunction "2_2") (pintype "input"))
      (node (ref "U8") (pin "4") (pinfunction "VSENSE_4") (pintype "unspecified"))
    )
    (net (code "61") (name "unconnected-(DATA-Pad12)") (class "Default")
      (node (ref "DATA") (pin "12") (pinfunction "12_12") (pintype "unspecified+no_connect"))
    )
    (net (code "62") (name "unconnected-(DATA-Pad13)") (class "Default")
      (node (ref "DATA") (pin "13") (pinfunction "13_13") (pintype "unspecified+no_connect"))
    )
    (net (code "63") (name "unconnected-(DATA-Pad14)") (class "Default")
      (node (ref "DATA") (pin "14") (pinfunction "14_14") (pintype "unspecified+no_connect"))
    )
    (net (code "64") (name "unconnected-(DATA-Pad15)") (class "Default")
      (node (ref "DATA") (pin "15") (pinfunction "15_15") (pintype "unspecified+no_connect"))
    )
    (net (code "65") (name "unconnected-(DATA-SBU1-PadA8)") (class "Default")
      (node (ref "DATA") (pin "A8") (pinfunction "SBU1_A8") (pintype "unspecified+no_connect"))
    )
    (net (code "66") (name "unconnected-(DATA-SBU2-PadB8)") (class "Default")
      (node (ref "DATA") (pin "B8") (pinfunction "SBU2_B8") (pintype "unspecified+no_connect"))
    )
    (net (code "67") (name "unconnected-(PD-DN1-PadA7)") (class "Default")
      (node (ref "PD") (pin "A7") (pinfunction "DN1_A7") (pintype "unspecified+no_connect"))
    )
    (net (code "68") (name "unconnected-(PD-DN2-PadB7)") (class "Default")
      (node (ref "PD") (pin "B7") (pinfunction "DN2_B7") (pintype "unspecified+no_connect"))
    )
    (net (code "69") (name "unconnected-(PD-DP1-PadA6)") (class "Default")
      (node (ref "PD") (pin "A6") (pinfunction "DP1_A6") (pintype "unspecified+no_connect"))
    )
    (net (code "70") (name "unconnected-(PD-DP2-PadB6)") (class "Default")
      (node (ref "PD") (pin "B6") (pinfunction "DP2_B6") (pintype "unspecified+no_connect"))
    )
    (net (code "71") (name "unconnected-(PD-Pad12)") (class "Default")
      (node (ref "PD") (pin "12") (pinfunction "12_12") (pintype "unspecified+no_connect"))
    )
    (net (code "72") (name "unconnected-(PD-Pad13)") (class "Default")
      (node (ref "PD") (pin "13") (pinfunction "13_13") (pintype "unspecified+no_connect"))
    )
    (net (code "73") (name "unconnected-(PD-Pad14)") (class "Default")
      (node (ref "PD") (pin "14") (pinfunction "14_14") (pintype "unspecified+no_connect"))
    )
    (net (code "74") (name "unconnected-(PD-Pad15)") (class "Default")
      (node (ref "PD") (pin "15") (pinfunction "15_15") (pintype "unspecified+no_connect"))
    )
    (net (code "75") (name "unconnected-(PD-SBU1-PadA8)") (class "Default")
      (node (ref "PD") (pin "A8") (pinfunction "SBU1_A8") (pintype "unspecified+no_connect"))
    )
    (net (code "76") (name "unconnected-(PD-SBU2-PadB8)") (class "Default")
      (node (ref "PD") (pin "B8") (pinfunction "SBU2_B8") (pintype "unspecified+no_connect"))
    )
    (net (code "77") (name "unconnected-(SYSFAN1-Pad3)") (class "Default")
      (node (ref "SYSFAN1") (pin "3") (pinfunction "3_3") (pintype "bidirectional+no_connect"))
    )
    (net (code "78") (name "unconnected-(SYSFAN1-Pad4)") (class "Default")
      (node (ref "SYSFAN1") (pin "4") (pinfunction "4_4") (pintype "bidirectional+no_connect"))
    )
    (net (code "79") (name "unconnected-(U1-EP-Pad17)") (class "Default")
      (node (ref "U1") (pin "17") (pinfunction "EP_17") (pintype "unspecified+no_connect"))
    )
    (net (code "80") (name "unconnected-(U1-NC-Pad1)") (class "Default")
      (node (ref "U1") (pin "1") (pinfunction "NC_1") (pintype "unspecified+no_connect"))
    )
    (net (code "81") (name "unconnected-(U1-NC-Pad2)") (class "Default")
      (node (ref "U1") (pin "2") (pinfunction "NC_2") (pintype "unspecified+no_connect"))
    )
    (net (code "82") (name "unconnected-(U1-NC-Pad3)") (class "Default")
      (node (ref "U1") (pin "3") (pinfunction "NC_3") (pintype "unspecified+no_connect"))
    )
    (net (code "83") (name "unconnected-(U1-NC-Pad4)") (class "Default")
      (node (ref "U1") (pin "4") (pinfunction "NC_4") (pintype "unspecified+no_connect"))
    )
    (net (code "84") (name "unconnected-(U1-NC-Pad10)") (class "Default")
      (node (ref "U1") (pin "10") (pinfunction "NC_10") (pintype "unspecified+no_connect"))
    )
    (net (code "85") (name "unconnected-(U1-OUT-Pad15)") (class "Default")
      (node (ref "U1") (pin "15") (pinfunction "OUT_15") (pintype "unspecified+no_connect"))
    )
    (net (code "86") (name "unconnected-(U1-PUSH-Pad5)") (class "Default")
      (node (ref "U1") (pin "5") (pinfunction "PUSH_5") (pintype "unspecified+no_connect"))
    )
    (net (code "87") (name "unconnected-(U1-U-Pad11)") (class "Default")
      (node (ref "U1") (pin "11") (pinfunction "U_11") (pintype "unspecified+no_connect"))
    )
    (net (code "88") (name "unconnected-(U1-V-Pad12)") (class "Default")
      (node (ref "U1") (pin "12") (pinfunction "V_12") (pintype "unspecified+no_connect"))
    )
    (net (code "89") (name "unconnected-(U1-W-Pad9)") (class "Default")
      (node (ref "U1") (pin "9") (pinfunction "W_9") (pintype "unspecified+no_connect"))
    )
    (net (code "90") (name "unconnected-(U2-COMPO#-Pad19)") (class "Default")
      (node (ref "U2") (pin "19") (pinfunction "COMPO#_19") (pintype "unspecified+no_connect"))
    )
    (net (code "91") (name "unconnected-(U2-NC-Pad21)") (class "Default")
      (node (ref "U2") (pin "21") (pinfunction "NC_21") (pintype "unspecified+no_connect"))
    )
    (net (code "92") (name "unconnected-(U4-CFG1-Pad9)") (class "Default")
      (node (ref "U4") (pin "9") (pinfunction "CFG1_9") (pintype "unspecified+no_connect"))
    )
    (net (code "93") (name "unconnected-(U4-CFG2-Pad2)") (class "Default")
      (node (ref "U4") (pin "2") (pinfunction "CFG2_2") (pintype "unspecified+no_connect"))
    )
    (net (code "94") (name "unconnected-(U4-CFG3-Pad3)") (class "Default")
      (node (ref "U4") (pin "3") (pinfunction "CFG3_3") (pintype "unspecified+no_connect"))
    )
    (net (code "95") (name "unconnected-(U4-DM-Pad5)") (class "Default")
      (node (ref "U4") (pin "5") (pinfunction "DM_5") (pintype "unspecified+no_connect"))
    )
    (net (code "96") (name "unconnected-(U4-DP-Pad4)") (class "Default")
      (node (ref "U4") (pin "4") (pinfunction "DP_4") (pintype "unspecified+no_connect"))
    )
    (net (code "97") (name "unconnected-(U4-PG-Pad10)") (class "Default")
      (node (ref "U4") (pin "10") (pinfunction "PG_10") (pintype "unspecified+no_connect"))
    )
    (net (code "98") (name "unconnected-(U5-IO15-Pad23)") (class "Default")
      (node (ref "U5") (pin "23") (pinfunction "IO15_23") (pintype "unspecified+no_connect"))
    )
    (net (code "99") (name "unconnected-(U5-IO32-Pad8)") (class "Default")
      (node (ref "U5") (pin "8") (pinfunction "IO32_8") (pintype "unspecified+no_connect"))
    )
    (net (code "100") (name "unconnected-(U5-IO34-Pad6)") (class "Default")
      (node (ref "U5") (pin "6") (pinfunction "IO34_6") (pintype "unspecified+no_connect"))
    )
    (net (code "101") (name "unconnected-(U5-IO35-Pad7)") (class "Default")
      (node (ref "U5") (pin "7") (pinfunction "IO35_7") (pintype "unspecified+no_connect"))
    )
    (net (code "102") (name "unconnected-(U5-NC-Pad17)") (class "Default")
      (node (ref "U5") (pin "17") (pinfunction "NC_17") (pintype "unspecified+no_connect"))
    )
    (net (code "103") (name "unconnected-(U5-NC-Pad18)") (class "Default")
      (node (ref "U5") (pin "18") (pinfunction "NC_18") (pintype "unspecified+no_connect"))
    )
    (net (code "104") (name "unconnected-(U5-NC-Pad19)") (class "Default")
      (node (ref "U5") (pin "19") (pinfunction "NC_19") (pintype "unspecified+no_connect"))
    )
    (net (code "105") (name "unconnected-(U5-NC-Pad20)") (class "Default")
      (node (ref "U5") (pin "20") (pinfunction "NC_20") (pintype "unspecified+no_connect"))
    )
    (net (code "106") (name "unconnected-(U5-NC-Pad21)") (class "Default")
      (node (ref "U5") (pin "21") (pinfunction "NC_21") (pintype "unspecified+no_connect"))
    )
    (net (code "107") (name "unconnected-(U5-NC-Pad22)") (class "Default")
      (node (ref "U5") (pin "22") (pinfunction "NC_22") (pintype "unspecified+no_connect"))
    )
    (net (code "108") (name "unconnected-(U5-NC-Pad32)") (class "Default")
      (node (ref "U5") (pin "32") (pinfunction "NC_32") (pintype "unspecified+no_connect"))
    )
    (net (code "109") (name "unconnected-(U5-SENSOR_VN-Pad5)") (class "Default")
      (node (ref "U5") (pin "5") (pinfunction "SENSOR_VN_5") (pintype "unspecified+no_connect"))
    )
    (net (code "110") (name "unconnected-(U5-SENSOR_VP-Pad4)") (class "Default")
      (node (ref "U5") (pin "4") (pinfunction "SENSOR_VP_4") (pintype "unspecified+no_connect"))
    )
    (net (code "111") (name "unconnected-(U6-ENA-Pad5)") (class "Default")
      (node (ref "U6") (pin "5") (pinfunction "ENA_5") (pintype "unspecified+no_connect"))
    )
    (net (code "112") (name "unconnected-(U6-NC-Pad2)") (class "Default")
      (node (ref "U6") (pin "2") (pinfunction "NC_2") (pintype "unspecified+no_connect"))
    )
    (net (code "113") (name "unconnected-(U6-NC-Pad3)") (class "Default")
      (node (ref "U6") (pin "3") (pinfunction "NC_3") (pintype "unspecified+no_connect"))
    )
    (net (code "114") (name "unconnected-(U7-CTS-Pad23)") (class "Default")
      (node (ref "U7") (pin "23") (pinfunction "CTS_23") (pintype "unspecified+no_connect"))
    )
    (net (code "115") (name "unconnected-(U7-DCD-Pad1)") (class "Default")
      (node (ref "U7") (pin "1") (pinfunction "DCD_1") (pintype "unspecified+no_connect"))
    )
    (net (code "116") (name "unconnected-(U7-DSR-Pad27)") (class "Default")
      (node (ref "U7") (pin "27") (pinfunction "DSR_27") (pintype "unspecified+no_connect"))
    )
    (net (code "117") (name "unconnected-(U7-NC-Pad10)") (class "Default")
      (node (ref "U7") (pin "10") (pinfunction "NC_10") (pintype "unspecified+no_connect"))
    )
    (net (code "118") (name "unconnected-(U7-NC-Pad13)") (class "Default")
      (node (ref "U7") (pin "13") (pinfunction "NC_13") (pintype "unspecified+no_connect"))
    )
    (net (code "119") (name "unconnected-(U7-NC-Pad14)") (class "Default")
      (node (ref "U7") (pin "14") (pinfunction "NC_14") (pintype "unspecified+no_connect"))
    )
    (net (code "120") (name "unconnected-(U7-NC-Pad15)") (class "Default")
      (node (ref "U7") (pin "15") (pinfunction "NC_15") (pintype "unspecified+no_connect"))
    )
    (net (code "121") (name "unconnected-(U7-NC-Pad16)") (class "Default")
      (node (ref "U7") (pin "16") (pinfunction "NC_16") (pintype "unspecified+no_connect"))
    )
    (net (code "122") (name "unconnected-(U7-NC-Pad17)") (class "Default")
      (node (ref "U7") (pin "17") (pinfunction "NC_17") (pintype "unspecified+no_connect"))
    )
    (net (code "123") (name "unconnected-(U7-NC-Pad18)") (class "Default")
      (node (ref "U7") (pin "18") (pinfunction "NC_18") (pintype "unspecified+no_connect"))
    )
    (net (code "124") (name "unconnected-(U7-NC-Pad19)") (class "Default")
      (node (ref "U7") (pin "19") (pinfunction "NC_19") (pintype "unspecified+no_connect"))
    )
    (net (code "125") (name "unconnected-(U7-NC-Pad20)") (class "Default")
      (node (ref "U7") (pin "20") (pinfunction "NC_20") (pintype "unspecified+no_connect"))
    )
    (net (code "126") (name "unconnected-(U7-NC-Pad21)") (class "Default")
      (node (ref "U7") (pin "21") (pinfunction "NC_21") (pintype "unspecified+no_connect"))
    )
    (net (code "127") (name "unconnected-(U7-NC-Pad22)") (class "Default")
      (node (ref "U7") (pin "22") (pinfunction "NC_22") (pintype "unspecified+no_connect"))
    )
    (net (code "128") (name "unconnected-(U7-RI-Pad2)") (class "Default")
      (node (ref "U7") (pin "2") (pinfunction "RI_2") (pintype "unspecified+no_connect"))
    )
    (net (code "129") (name "unconnected-(U7-SUSPEND#-Pad11)") (class "Default")
      (node (ref "U7") (pin "11") (pinfunction "SUSPEND#_11") (pintype "unspecified+no_connect"))
    )
    (net (code "130") (name "unconnected-(U7-SUSPEND-Pad12)") (class "Default")
      (node (ref "U7") (pin "12") (pinfunction "SUSPEND_12") (pintype "unspecified+no_connect"))
    )
    (net (code "131") (name "unconnected-(U8-ENA-Pad5)") (class "Default")
      (node (ref "U8") (pin "5") (pinfunction "ENA_5") (pintype "unspecified+no_connect"))
    )
    (net (code "132") (name "unconnected-(U8-NC-Pad2)") (class "Default")
      (node (ref "U8") (pin "2") (pinfunction "NC_2") (pintype "unspecified+no_connect"))
    )
    (net (code "133") (name "unconnected-(U8-NC-Pad3)") (class "Default")
      (node (ref "U8") (pin "3") (pinfunction "NC_3") (pintype "unspecified+no_connect"))
    )
  )
)
